# TH8_Breakout_cryo.net
KiCad netlist of a schematic drawn in Altium Designer
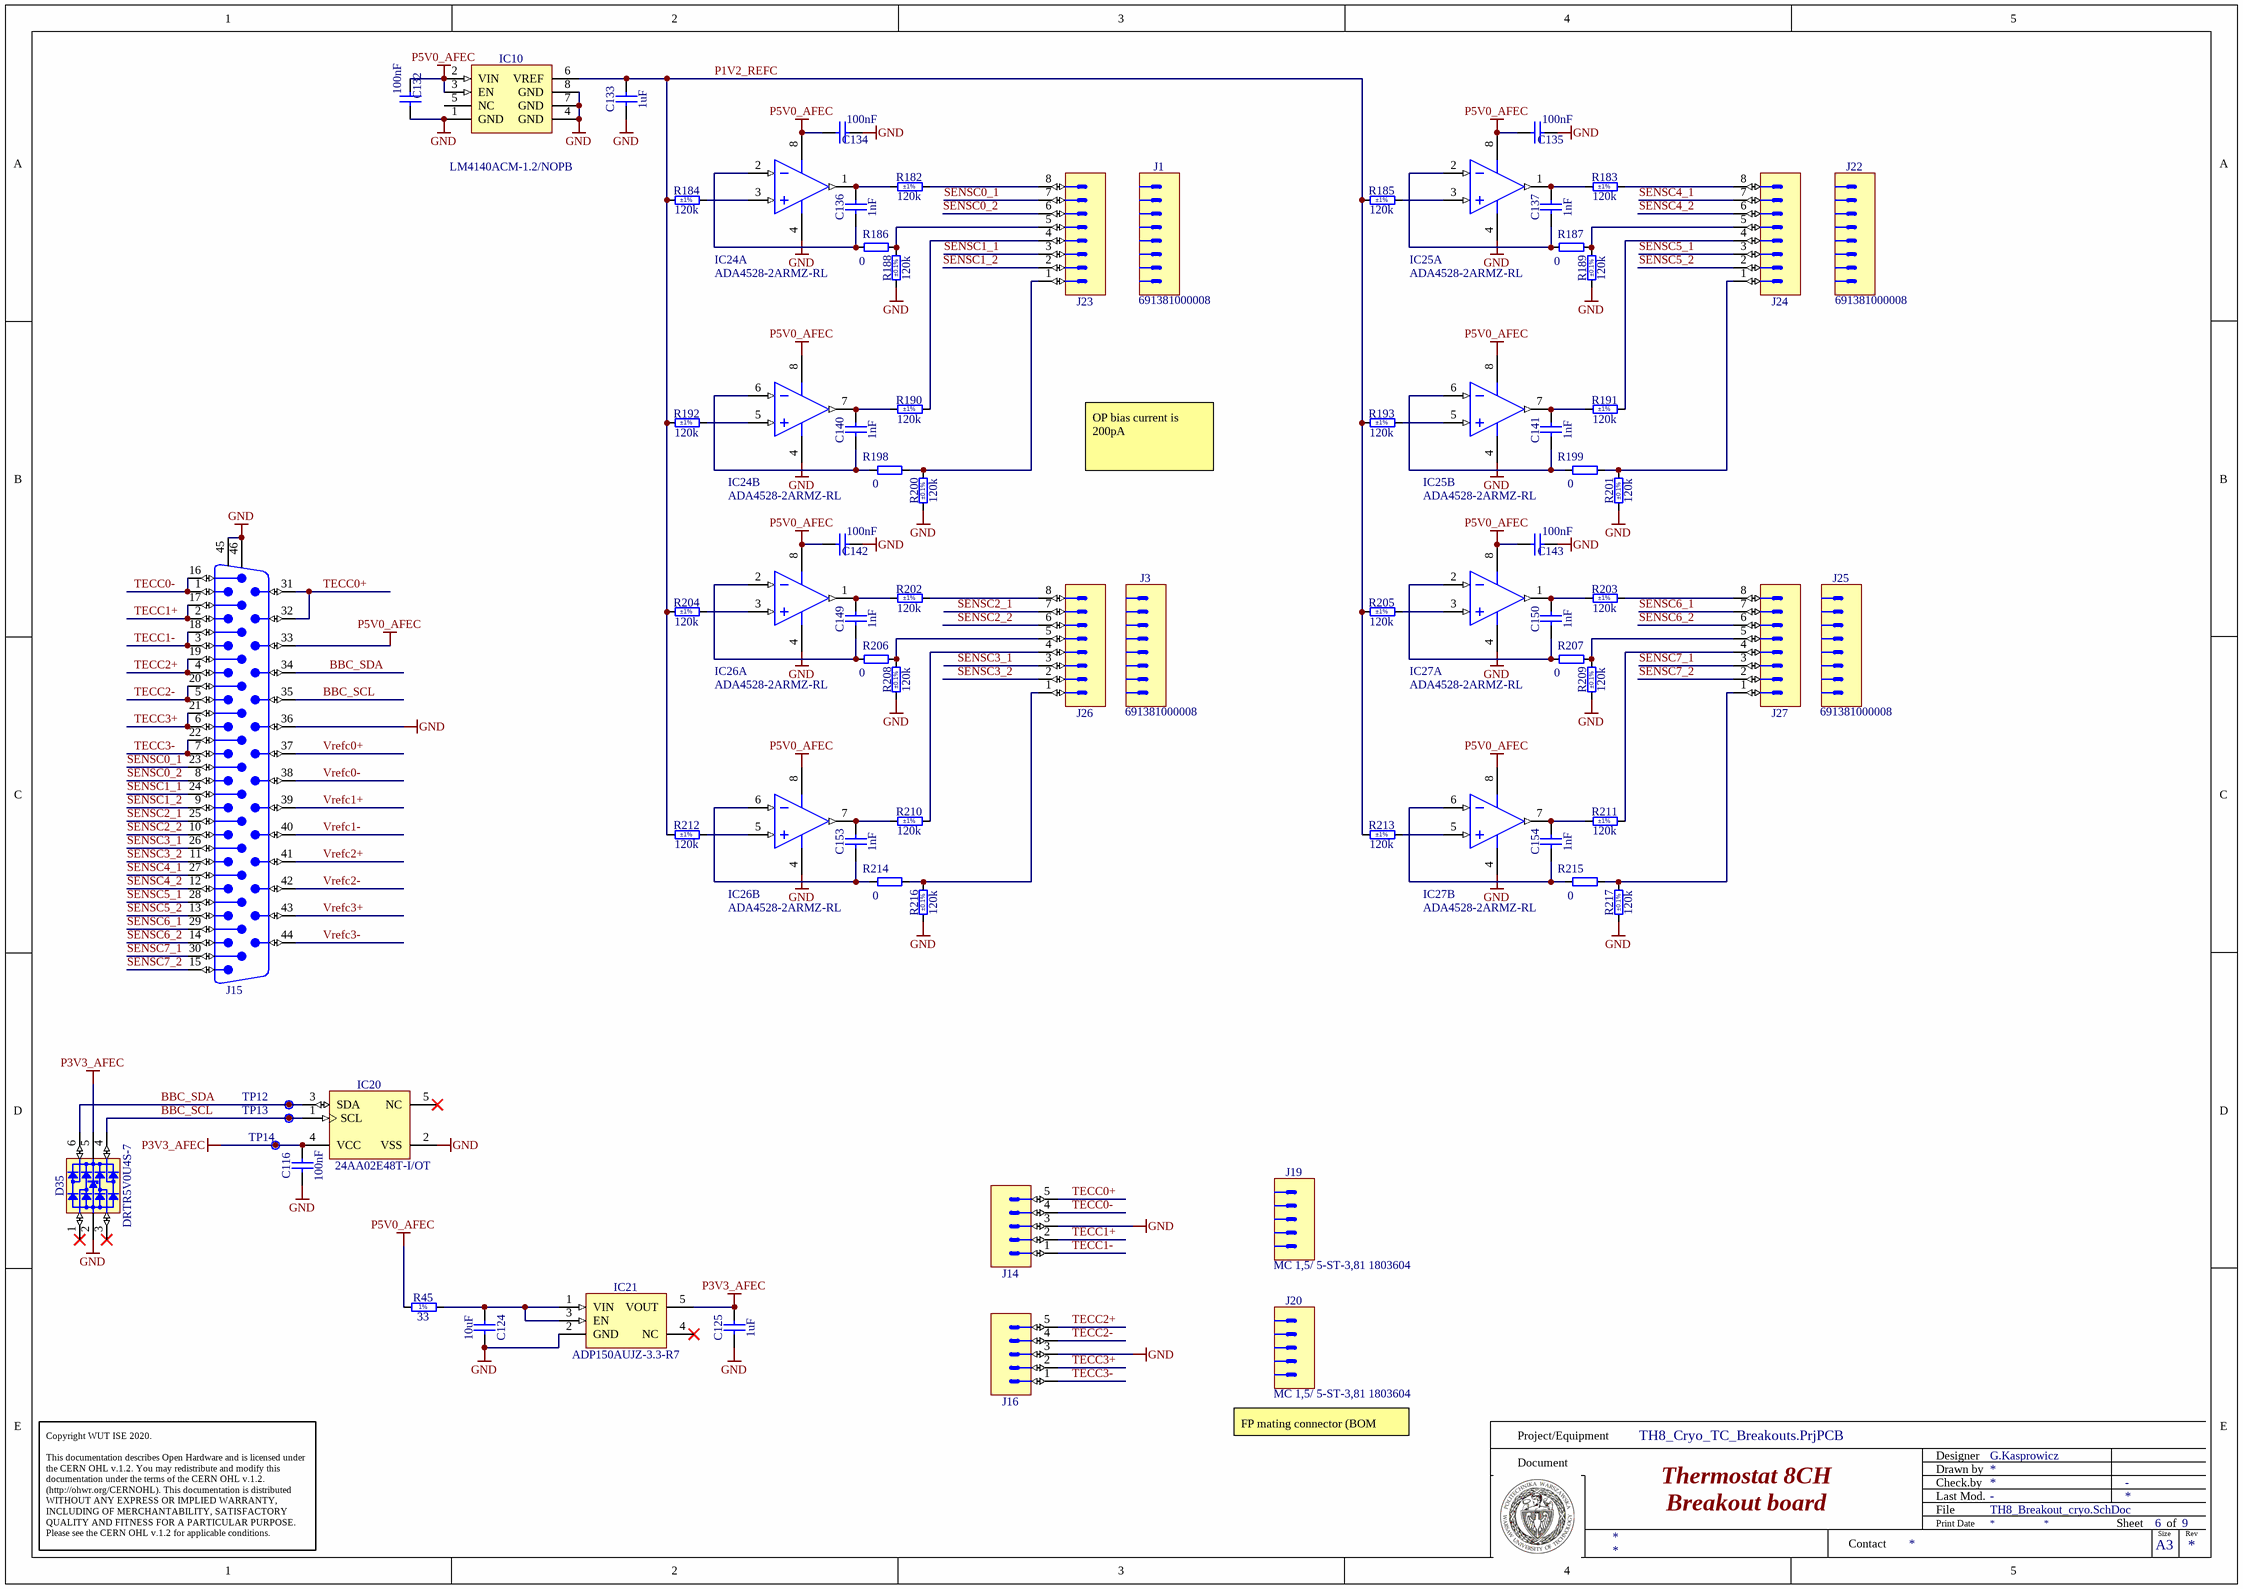
[diagram p0: TH8_Breakout_cryo.SchDoc]

(export (version "E")
  (design (tool "Eeschema 10.0.6"))
  (components
    (comp (ref "C116")
      (value "100nF")
      (footprint "CAPC1005X55N")
      (description "Non-polarised capacitor")
      (fields
        (field (name "PART NUMBER") "CC0402_100NF_16V_10%_X5R")
        (field (name "VOLTAGE") "16V")
        (field (name "AUTHOR") "CERN DEM JLC")
      )
      (libsource (lib "Capacitors") (part "Capacitor - non polarized"))
    )
    (comp (ref "C124")
      (value "10uF")
      (footprint "CAPC2012X135N")
      (description "Non-polarised capacitor")
      (fields
        (field (name "PART NUMBER") "CC0805_10UF_16V_10%_X5R")
        (field (name "VOLTAGE") "16V")
        (field (name "AUTHOR") "CERN DEM JLC")
      )
      (libsource (lib "Capacitors") (part "Capacitor - non polarized"))
    )
    (comp (ref "C125")
      (value "1uF")
      (footprint "CAPC1608X87N")
      (description "Non-polarised capacitor")
      (fields
        (field (name "PART NUMBER") "CC0603_1UF_25V_10%_X7R")
        (field (name "VOLTAGE") "25V")
        (field (name "AUTHOR") "CERN DEM JLC")
      )
      (libsource (lib "Capacitors") (part "Capacitor - non polarized"))
    )
    (comp (ref "C132")
      (value "100nF")
      (footprint "CAPC1005X55N")
      (description "Non-polarised capacitor")
      (fields
        (field (name "PART NUMBER") "CC0402_100NF_16V_10%_X5R")
        (field (name "VOLTAGE") "16V")
        (field (name "AUTHOR") "CERN DEM JLC")
      )
      (libsource (lib "Capacitors") (part "Capacitor - non polarized"))
    )
    (comp (ref "C133")
      (value "1uF")
      (footprint "CAPC1608X87N")
      (description "Non-polarised capacitor")
      (fields
        (field (name "PART NUMBER") "CC0603_1UF_25V_10%_X7R")
        (field (name "VOLTAGE") "25V")
        (field (name "AUTHOR") "CERN DEM JLC")
      )
      (libsource (lib "Capacitors") (part "Capacitor - non polarized"))
    )
    (comp (ref "C134")
      (value "100nF")
      (footprint "CAPC1005X55N")
      (description "Non-polarised capacitor")
      (fields
        (field (name "PART NUMBER") "CC0402_100NF_16V_10%_X5R")
        (field (name "VOLTAGE") "16V")
        (field (name "AUTHOR") "CERN DEM JLC")
      )
      (libsource (lib "Capacitors") (part "Capacitor - non polarized"))
    )
    (comp (ref "C135")
      (value "100nF")
      (footprint "CAPC1005X55N")
      (description "Non-polarised capacitor")
      (fields
        (field (name "PART NUMBER") "CC0402_100NF_16V_10%_X5R")
        (field (name "VOLTAGE") "16V")
        (field (name "AUTHOR") "CERN DEM JLC")
      )
      (libsource (lib "Capacitors") (part "Capacitor - non polarized"))
    )
    (comp (ref "C136")
      (value "1nF")
      (footprint "CAPC1005X55N")
      (description "Non-polarised capacitor")
      (fields
        (field (name "PART NUMBER") "CC0402_1NF_50V_10%_X7R")
        (field (name "VOLTAGE") "50V")
        (field (name "AUTHOR") "CERN DEM JLC")
      )
      (libsource (lib "Capacitors") (part "Capacitor - non polarized"))
    )
    (comp (ref "C137")
      (value "1nF")
      (footprint "CAPC1005X55N")
      (description "Non-polarised capacitor")
      (fields
        (field (name "PART NUMBER") "CC0402_1NF_50V_10%_X7R")
        (field (name "VOLTAGE") "50V")
        (field (name "AUTHOR") "CERN DEM JLC")
      )
      (libsource (lib "Capacitors") (part "Capacitor - non polarized"))
    )
    (comp (ref "C140")
      (value "1nF")
      (footprint "CAPC1005X55N")
      (description "Non-polarised capacitor")
      (fields
        (field (name "PART NUMBER") "CC0402_1NF_50V_10%_X7R")
        (field (name "VOLTAGE") "50V")
        (field (name "AUTHOR") "CERN DEM JLC")
      )
      (libsource (lib "Capacitors") (part "Capacitor - non polarized"))
    )
    (comp (ref "C141")
      (value "1nF")
      (footprint "CAPC1005X55N")
      (description "Non-polarised capacitor")
      (fields
        (field (name "PART NUMBER") "CC0402_1NF_50V_10%_X7R")
        (field (name "VOLTAGE") "50V")
        (field (name "AUTHOR") "CERN DEM JLC")
      )
      (libsource (lib "Capacitors") (part "Capacitor - non polarized"))
    )
    (comp (ref "C142")
      (value "100nF")
      (footprint "CAPC1005X55N")
      (description "Non-polarised capacitor")
      (fields
        (field (name "PART NUMBER") "CC0402_100NF_16V_10%_X5R")
        (field (name "VOLTAGE") "16V")
        (field (name "AUTHOR") "CERN DEM JLC")
      )
      (libsource (lib "Capacitors") (part "Capacitor - non polarized"))
    )
    (comp (ref "C143")
      (value "100nF")
      (footprint "CAPC1005X55N")
      (description "Non-polarised capacitor")
      (fields
        (field (name "PART NUMBER") "CC0402_100NF_16V_10%_X5R")
        (field (name "VOLTAGE") "16V")
        (field (name "AUTHOR") "CERN DEM JLC")
      )
      (libsource (lib "Capacitors") (part "Capacitor - non polarized"))
    )
    (comp (ref "C149")
      (value "1nF")
      (footprint "CAPC1005X55N")
      (description "Non-polarised capacitor")
      (fields
        (field (name "PART NUMBER") "CC0402_1NF_50V_10%_X7R")
        (field (name "VOLTAGE") "50V")
        (field (name "AUTHOR") "CERN DEM JLC")
      )
      (libsource (lib "Capacitors") (part "Capacitor - non polarized"))
    )
    (comp (ref "C150")
      (value "1nF")
      (footprint "CAPC1005X55N")
      (description "Non-polarised capacitor")
      (fields
        (field (name "PART NUMBER") "CC0402_1NF_50V_10%_X7R")
        (field (name "VOLTAGE") "50V")
        (field (name "AUTHOR") "CERN DEM JLC")
      )
      (libsource (lib "Capacitors") (part "Capacitor - non polarized"))
    )
    (comp (ref "C153")
      (value "1nF")
      (footprint "CAPC1005X55N")
      (description "Non-polarised capacitor")
      (fields
        (field (name "PART NUMBER") "CC0402_1NF_50V_10%_X7R")
        (field (name "VOLTAGE") "50V")
        (field (name "AUTHOR") "CERN DEM JLC")
      )
      (libsource (lib "Capacitors") (part "Capacitor - non polarized"))
    )
    (comp (ref "C154")
      (value "1nF")
      (footprint "CAPC1005X55N")
      (description "Non-polarised capacitor")
      (fields
        (field (name "PART NUMBER") "CC0402_1NF_50V_10%_X7R")
        (field (name "VOLTAGE") "50V")
        (field (name "AUTHOR") "CERN DEM JLC")
      )
      (libsource (lib "Capacitors") (part "Capacitor - non polarized"))
    )
    (comp (ref "D35")
      (value "DRTR5V0U4S-7")
      (footprint "SOT65P210X110-6N")
      (description "Integrated Quad Ultra-Low Capacitance ESD Protection")
      (fields (field (name "MANUFACTURER") "DIODES") (field (name "AUTHOR") "GK"))
      (libsource (lib "Diodes") (part "D_TVS_DRTR5V0U4S-7"))
    )
    (comp (ref "IC10")
      (value "LM4140ACM-1.2/NOPB")
      (footprint "SOIC127P600X175-8N")
      (description "High Precision Low Noise Low Dropout Voltage Reference")
      (fields (field (name "MANUFACTURER") "TEXAS INSTRUMENTS") (field (name "AUTHOR") "CERN DEM JLC"))
      (libsource (lib "ICs And Semiconductors") (part "LM4140"))
    )
    (comp (ref "IC20")
      (value "24AA02E48T-I/OT")
      (footprint "SOT95P280X145-5N")
      (description "1.7V-5.5V, 2K I2C Serial EEPROM With EUI-48 Node Identity")
      (fields (field (name "MANUFACTURER") "MICROCHIP TECHNOLOGY") (field (name "AUTHOR") "CERN DEM MR"))
      (libsource (lib "ICs And Semiconductors") (part "24AA02E48T-I/OT"))
    )
    (comp (ref "IC21")
      (value "ADP150AUJZ-3.3-R7")
      (footprint "SOT95P280X90-5N")
      (description "Ultralow Noise, 150 mA CMOS Linear Regulator")
      (fields (field (name "MANUFACTURER") "ANALOG DEVICES") (field (name "AUTHOR") "CERN DEM JLC"))
      (libsource (lib "ICs And Semiconductors") (part "ADP150AUJZ"))
    )
    (comp (ref "IC24")
      (value "ADA4528-2ARMZ-RL")
      (footprint "ADI-RM-8_N")
      (fields (field (name "GENERIC PART NUMBER") "ADA4528-2") (field (name "MANUFACTURER") "Analog Devices"))
      (libsource (lib "Altium Content Vault") (part "ADI-ADA4000-2-X-8"))
    )
    (comp (ref "IC25")
      (value "ADA4528-2ARMZ-RL")
      (footprint "ADI-RM-8_N")
      (fields (field (name "GENERIC PART NUMBER") "ADA4528-2") (field (name "MANUFACTURER") "Analog Devices"))
      (libsource (lib "Altium Content Vault") (part "ADI-ADA4000-2-X-8"))
    )
    (comp (ref "IC26")
      (value "ADA4528-2ARMZ-RL")
      (footprint "ADI-RM-8_N")
      (fields (field (name "GENERIC PART NUMBER") "ADA4528-2") (field (name "MANUFACTURER") "Analog Devices"))
      (libsource (lib "Altium Content Vault") (part "ADI-ADA4000-2-X-8"))
    )
    (comp (ref "IC27")
      (value "ADA4528-2ARMZ-RL")
      (footprint "ADI-RM-8_N")
      (fields (field (name "GENERIC PART NUMBER") "ADA4528-2") (field (name "MANUFACTURER") "Analog Devices"))
      (libsource (lib "Altium Content Vault") (part "ADI-ADA4000-2-X-8"))
    )
    (comp (ref "J1")
      (value "691381000008")
      (footprint "WURTH_691381000008")
      (description "Phoenix Contact 2.5 pitch terminal plug, 8 ways")
      (fields (field (name "MANUFACTURER") "WURTH") (field (name "MANUFACTURER PART NUMBER") "691381000008"))
      (libsource (lib "Connectors") (part "CON_TB_WURTH_691381000008"))
    )
    (comp (ref "J3")
      (value "691381000008")
      (footprint "WURTH_691381000008")
      (description "Phoenix Contact 2.5 pitch terminal plug, 8 ways")
      (fields (field (name "MANUFACTURER") "WURTH") (field (name "MANUFACTURER PART NUMBER") "691381000008"))
      (libsource (lib "Connectors") (part "CON_TB_WURTH_691381000008"))
    )
    (comp (ref "J14")
      (value "~")
      (footprint "PHOENIX_1803455")
      (description "Connector 5 Male")
      (fields
        (field (name "PART NUMBER") "PHOENIX_1803455")
        (field (name "MANUFACTURER") "PHOENIX CONTACT")
        (field (name "AUTHOR") "CERN DEM JLC")
      )
      (libsource (lib "Connectors") (part "Connector 5 Male"))
    )
    (comp (ref "J15")
      (value "D-Sub")
      (footprint "AMPHENOL_10090926-P444XLF")
      (description "Connector D-sub 44 Male")
      (fields
        (field (name "PART NUMBER") "AMPHENOL_10090926-P444XLF")
        (field (name "MANUFACTURER") "AMPHENOL")
        (field (name "AUTHOR") "CERN DEM BC")
      )
      (libsource (lib "Connectors") (part "Connector D-sub 44 Male"))
    )
    (comp (ref "J16")
      (value "~")
      (footprint "PHOENIX_1803455")
      (description "Connector 5 Male")
      (fields
        (field (name "PART NUMBER") "PHOENIX_1803455")
        (field (name "MANUFACTURER") "PHOENIX CONTACT")
        (field (name "AUTHOR") "CERN DEM JLC")
      )
      (libsource (lib "Connectors") (part "Connector 5 Male"))
    )
    (comp (ref "J19")
      (value "~")
      (footprint "PHOENIX_1803604")
      (description "Phoenix Contact 3.81 pitch terminal plug, 5 ways")
      (fields
        (field (name "MANUFACTURER") "Phoenix Contact")
        (field (name "MANUFACTURER PART NUMBER") "MC 1,5/ 5-ST-3,81 1803604")
      )
      (libsource (lib "Connectors") (part "PHOENIX_1803604"))
    )
    (comp (ref "J20")
      (value "~")
      (footprint "PHOENIX_1803604")
      (description "Phoenix Contact 3.81 pitch terminal plug, 5 ways")
      (fields
        (field (name "MANUFACTURER") "Phoenix Contact")
        (field (name "MANUFACTURER PART NUMBER") "MC 1,5/ 5-ST-3,81 1803604")
      )
      (libsource (lib "Connectors") (part "PHOENIX_1803604"))
    )
    (comp (ref "J22")
      (value "691381000008")
      (footprint "WURTH_691381000008")
      (description "Phoenix Contact 2.5 pitch terminal plug, 8 ways")
      (fields (field (name "MANUFACTURER") "WURTH") (field (name "MANUFACTURER PART NUMBER") "691381000008"))
      (libsource (lib "Connectors") (part "CON_TB_WURTH_691381000008"))
    )
    (comp (ref "J23")
      (value "~")
      (footprint "PHOENIX_1881613")
      (description "Connector 8 Male")
      (fields
        (field (name "PART NUMBER") "PHOENIX_1881613")
        (field (name "MANUFACTURER") "PHOENIX CONTACT")
        (field (name "AUTHOR") "CERN DEM JLC")
      )
      (libsource (lib "Connectors") (part "Connector 8 Male"))
    )
    (comp (ref "J24")
      (value "~")
      (footprint "PHOENIX_1881613")
      (description "Connector 8 Male")
      (fields
        (field (name "PART NUMBER") "PHOENIX_1881613")
        (field (name "MANUFACTURER") "PHOENIX CONTACT")
        (field (name "AUTHOR") "CERN DEM JLC")
      )
      (libsource (lib "Connectors") (part "Connector 8 Male"))
    )
    (comp (ref "J25")
      (value "691381000008")
      (footprint "WURTH_691381000008")
      (description "Phoenix Contact 2.5 pitch terminal plug, 8 ways")
      (fields (field (name "MANUFACTURER") "WURTH") (field (name "MANUFACTURER PART NUMBER") "691381000008"))
      (libsource (lib "Connectors") (part "CON_TB_WURTH_691381000008"))
    )
    (comp (ref "J26")
      (value "~")
      (footprint "PHOENIX_1881613")
      (description "Connector 8 Male")
      (fields
        (field (name "PART NUMBER") "PHOENIX_1881613")
        (field (name "MANUFACTURER") "PHOENIX CONTACT")
        (field (name "AUTHOR") "CERN DEM JLC")
      )
      (libsource (lib "Connectors") (part "Connector 8 Male"))
    )
    (comp (ref "J27")
      (value "~")
      (footprint "PHOENIX_1881613")
      (description "Connector 8 Male")
      (fields
        (field (name "PART NUMBER") "PHOENIX_1881613")
        (field (name "MANUFACTURER") "PHOENIX CONTACT")
        (field (name "AUTHOR") "CERN DEM JLC")
      )
      (libsource (lib "Connectors") (part "Connector 8 Male"))
    )
    (comp (ref "R45")
      (value "33")
      (footprint "RESC1005X40N")
      (description "Resistor - 1%")
      (fields
        (field (name "PART NUMBER") "R0402_33R_1%_0.0625W_100PPM")
        (field (name "POWER") "0.0625W")
        (field (name "AUTHOR") "CERN DEM JLC")
      )
      (libsource (lib "Resistors") (part "Resistor - 1%"))
    )
    (comp (ref "R182")
      (value "120k")
      (footprint "RESC1005X40N")
      (description "Resistor - 1%")
      (fields
        (field (name "TOLERANCE") "±1%")
        (field (name "PART NUMBER") "R0402_120K_1%_0.0625W_100PPM")
        (field (name "POWER") "0.0625W")
        (field (name "AUTHOR") "CERN DEM JLC")
      )
      (libsource (lib "Resistors") (part "Resistor - 1%"))
    )
    (comp (ref "R183")
      (value "120k")
      (footprint "RESC1005X40N")
      (description "Resistor - 1%")
      (fields
        (field (name "TOLERANCE") "±1%")
        (field (name "PART NUMBER") "R0402_120K_1%_0.0625W_100PPM")
        (field (name "POWER") "0.0625W")
        (field (name "AUTHOR") "CERN DEM JLC")
      )
      (libsource (lib "Resistors") (part "Resistor - 1%"))
    )
    (comp (ref "R184")
      (value "120k")
      (footprint "RESC1005X40N")
      (description "Resistor - 1%")
      (fields
        (field (name "TOLERANCE") "±1%")
        (field (name "PART NUMBER") "R0402_120K_1%_0.0625W_100PPM")
        (field (name "POWER") "0.0625W")
        (field (name "AUTHOR") "CERN DEM JLC")
      )
      (libsource (lib "Resistors") (part "Resistor - 1%"))
    )
    (comp (ref "R185")
      (value "120k")
      (footprint "RESC1005X40N")
      (description "Resistor - 1%")
      (fields
        (field (name "TOLERANCE") "±1%")
        (field (name "PART NUMBER") "R0402_120K_1%_0.0625W_100PPM")
        (field (name "POWER") "0.0625W")
        (field (name "AUTHOR") "CERN DEM JLC")
      )
      (libsource (lib "Resistors") (part "Resistor - 1%"))
    )
    (comp (ref "R186")
      (value "0")
      (footprint "RESC1608X55N")
      (description "Resistor")
      (fields
        (field (name "PART NUMBER") "R0603_0R_JUMPER")
        (field (name "MANUFACTURER") "GENERIC")
        (field (name "AUTHOR") "CERN DEM JLC")
      )
      (libsource (lib "Resistors") (part "Resistor"))
    )
    (comp (ref "R187")
      (value "0")
      (footprint "RESC1608X55N")
      (description "Resistor")
      (fields
        (field (name "PART NUMBER") "R0603_0R_JUMPER")
        (field (name "MANUFACTURER") "GENERIC")
        (field (name "AUTHOR") "CERN DEM JLC")
      )
      (libsource (lib "Resistors") (part "Resistor"))
    )
    (comp (ref "R188")
      (value "120k")
      (footprint "RESC2012X60N")
      (description "Resistor - 0.1%")
      (fields
        (field (name "TOLERANCE") "±0.1%")
        (field (name "PART NUMBER") "R0805_120K_0.1%_0.125W_25PPM")
        (field (name "POWER") "0.125W")
        (field (name "AUTHOR") "CERN DEM JLC")
      )
      (libsource (lib "Resistors") (part "Resistor - 0.1%"))
    )
    (comp (ref "R189")
      (value "120k")
      (footprint "RESC2012X60N")
      (description "Resistor - 0.1%")
      (fields
        (field (name "TOLERANCE") "±0.1%")
        (field (name "PART NUMBER") "R0805_120K_0.1%_0.125W_25PPM")
        (field (name "POWER") "0.125W")
        (field (name "AUTHOR") "CERN DEM JLC")
      )
      (libsource (lib "Resistors") (part "Resistor - 0.1%"))
    )
    (comp (ref "R190")
      (value "120k")
      (footprint "RESC1005X40N")
      (description "Resistor - 1%")
      (fields
        (field (name "TOLERANCE") "±1%")
        (field (name "PART NUMBER") "R0402_120K_1%_0.0625W_100PPM")
        (field (name "POWER") "0.0625W")
        (field (name "AUTHOR") "CERN DEM JLC")
      )
      (libsource (lib "Resistors") (part "Resistor - 1%"))
    )
    (comp (ref "R191")
      (value "120k")
      (footprint "RESC1005X40N")
      (description "Resistor - 1%")
      (fields
        (field (name "TOLERANCE") "±1%")
        (field (name "PART NUMBER") "R0402_120K_1%_0.0625W_100PPM")
        (field (name "POWER") "0.0625W")
        (field (name "AUTHOR") "CERN DEM JLC")
      )
      (libsource (lib "Resistors") (part "Resistor - 1%"))
    )
    (comp (ref "R192")
      (value "120k")
      (footprint "RESC1005X40N")
      (description "Resistor - 1%")
      (fields
        (field (name "TOLERANCE") "±1%")
        (field (name "PART NUMBER") "R0402_120K_1%_0.0625W_100PPM")
        (field (name "POWER") "0.0625W")
        (field (name "AUTHOR") "CERN DEM JLC")
      )
      (libsource (lib "Resistors") (part "Resistor - 1%"))
    )
    (comp (ref "R193")
      (value "120k")
      (footprint "RESC1005X40N")
      (description "Resistor - 1%")
      (fields
        (field (name "TOLERANCE") "±1%")
        (field (name "PART NUMBER") "R0402_120K_1%_0.0625W_100PPM")
        (field (name "POWER") "0.0625W")
        (field (name "AUTHOR") "CERN DEM JLC")
      )
      (libsource (lib "Resistors") (part "Resistor - 1%"))
    )
    (comp (ref "R198")
      (value "0")
      (footprint "RESC1608X55N")
      (description "Resistor")
      (fields
        (field (name "PART NUMBER") "R0603_0R_JUMPER")
        (field (name "MANUFACTURER") "GENERIC")
        (field (name "AUTHOR") "CERN DEM JLC")
      )
      (libsource (lib "Resistors") (part "Resistor"))
    )
    (comp (ref "R199")
      (value "0")
      (footprint "RESC1608X55N")
      (description "Resistor")
      (fields
        (field (name "PART NUMBER") "R0603_0R_JUMPER")
        (field (name "MANUFACTURER") "GENERIC")
        (field (name "AUTHOR") "CERN DEM JLC")
      )
      (libsource (lib "Resistors") (part "Resistor"))
    )
    (comp (ref "R200")
      (value "120k")
      (footprint "RESC2012X60N")
      (description "Resistor - 0.1%")
      (fields
        (field (name "TOLERANCE") "±0.1%")
        (field (name "PART NUMBER") "R0805_120K_0.1%_0.125W_25PPM")
        (field (name "POWER") "0.125W")
        (field (name "AUTHOR") "CERN DEM JLC")
      )
      (libsource (lib "Resistors") (part "Resistor - 0.1%"))
    )
    (comp (ref "R201")
      (value "120k")
      (footprint "RESC2012X60N")
      (description "Resistor - 0.1%")
      (fields
        (field (name "TOLERANCE") "±0.1%")
        (field (name "PART NUMBER") "R0805_120K_0.1%_0.125W_25PPM")
        (field (name "POWER") "0.125W")
        (field (name "AUTHOR") "CERN DEM JLC")
      )
      (libsource (lib "Resistors") (part "Resistor - 0.1%"))
    )
    (comp (ref "R202")
      (value "120k")
      (footprint "RESC1005X40N")
      (description "Resistor - 1%")
      (fields
        (field (name "TOLERANCE") "±1%")
        (field (name "PART NUMBER") "R0402_120K_1%_0.0625W_100PPM")
        (field (name "POWER") "0.0625W")
        (field (name "AUTHOR") "CERN DEM JLC")
      )
      (libsource (lib "Resistors") (part "Resistor - 1%"))
    )
    (comp (ref "R203")
      (value "120k")
      (footprint "RESC1005X40N")
      (description "Resistor - 1%")
      (fields
        (field (name "TOLERANCE") "±1%")
        (field (name "PART NUMBER") "R0402_120K_1%_0.0625W_100PPM")
        (field (name "POWER") "0.0625W")
        (field (name "AUTHOR") "CERN DEM JLC")
      )
      (libsource (lib "Resistors") (part "Resistor - 1%"))
    )
    (comp (ref "R204")
      (value "120k")
      (footprint "RESC1005X40N")
      (description "Resistor - 1%")
      (fields
        (field (name "TOLERANCE") "±1%")
        (field (name "PART NUMBER") "R0402_120K_1%_0.0625W_100PPM")
        (field (name "POWER") "0.0625W")
        (field (name "AUTHOR") "CERN DEM JLC")
      )
      (libsource (lib "Resistors") (part "Resistor - 1%"))
    )
    (comp (ref "R205")
      (value "120k")
      (footprint "RESC1005X40N")
      (description "Resistor - 1%")
      (fields
        (field (name "TOLERANCE") "±1%")
        (field (name "PART NUMBER") "R0402_120K_1%_0.0625W_100PPM")
        (field (name "POWER") "0.0625W")
        (field (name "AUTHOR") "CERN DEM JLC")
      )
      (libsource (lib "Resistors") (part "Resistor - 1%"))
    )
    (comp (ref "R206")
      (value "0")
      (footprint "RESC1608X55N")
      (description "Resistor")
      (fields
        (field (name "PART NUMBER") "R0603_0R_JUMPER")
        (field (name "MANUFACTURER") "GENERIC")
        (field (name "AUTHOR") "CERN DEM JLC")
      )
      (libsource (lib "Resistors") (part "Resistor"))
    )
    (comp (ref "R207")
      (value "0")
      (footprint "RESC1608X55N")
      (description "Resistor")
      (fields
        (field (name "PART NUMBER") "R0603_0R_JUMPER")
        (field (name "MANUFACTURER") "GENERIC")
        (field (name "AUTHOR") "CERN DEM JLC")
      )
      (libsource (lib "Resistors") (part "Resistor"))
    )
    (comp (ref "R208")
      (value "120k")
      (footprint "RESC2012X60N")
      (description "Resistor - 0.1%")
      (fields
        (field (name "TOLERANCE") "±0.1%")
        (field (name "PART NUMBER") "R0805_120K_0.1%_0.125W_25PPM")
        (field (name "POWER") "0.125W")
        (field (name "AUTHOR") "CERN DEM JLC")
      )
      (libsource (lib "Resistors") (part "Resistor - 0.1%"))
    )
    (comp (ref "R209")
      (value "120k")
      (footprint "RESC2012X60N")
      (description "Resistor - 0.1%")
      (fields
        (field (name "TOLERANCE") "±0.1%")
        (field (name "PART NUMBER") "R0805_120K_0.1%_0.125W_25PPM")
        (field (name "POWER") "0.125W")
        (field (name "AUTHOR") "CERN DEM JLC")
      )
      (libsource (lib "Resistors") (part "Resistor - 0.1%"))
    )
    (comp (ref "R210")
      (value "120k")
      (footprint "RESC1005X40N")
      (description "Resistor - 1%")
      (fields
        (field (name "TOLERANCE") "±1%")
        (field (name "PART NUMBER") "R0402_120K_1%_0.0625W_100PPM")
        (field (name "POWER") "0.0625W")
        (field (name "AUTHOR") "CERN DEM JLC")
      )
      (libsource (lib "Resistors") (part "Resistor - 1%"))
    )
    (comp (ref "R211")
      (value "120k")
      (footprint "RESC1005X40N")
      (description "Resistor - 1%")
      (fields
        (field (name "TOLERANCE") "±1%")
        (field (name "PART NUMBER") "R0402_120K_1%_0.0625W_100PPM")
        (field (name "POWER") "0.0625W")
        (field (name "AUTHOR") "CERN DEM JLC")
      )
      (libsource (lib "Resistors") (part "Resistor - 1%"))
    )
    (comp (ref "R212")
      (value "120k")
      (footprint "RESC1005X40N")
      (description "Resistor - 1%")
      (fields
        (field (name "TOLERANCE") "±1%")
        (field (name "PART NUMBER") "R0402_120K_1%_0.0625W_100PPM")
        (field (name "POWER") "0.0625W")
        (field (name "AUTHOR") "CERN DEM JLC")
      )
      (libsource (lib "Resistors") (part "Resistor - 1%"))
    )
    (comp (ref "R213")
      (value "120k")
      (footprint "RESC1005X40N")
      (description "Resistor - 1%")
      (fields
        (field (name "TOLERANCE") "±1%")
        (field (name "PART NUMBER") "R0402_120K_1%_0.0625W_100PPM")
        (field (name "POWER") "0.0625W")
        (field (name "AUTHOR") "CERN DEM JLC")
      )
      (libsource (lib "Resistors") (part "Resistor - 1%"))
    )
    (comp (ref "R214")
      (value "0")
      (footprint "RESC1608X55N")
      (description "Resistor")
      (fields
        (field (name "PART NUMBER") "R0603_0R_JUMPER")
        (field (name "MANUFACTURER") "GENERIC")
        (field (name "AUTHOR") "CERN DEM JLC")
      )
      (libsource (lib "Resistors") (part "Resistor"))
    )
    (comp (ref "R215")
      (value "0")
      (footprint "RESC1608X55N")
      (description "Resistor")
      (fields
        (field (name "PART NUMBER") "R0603_0R_JUMPER")
        (field (name "MANUFACTURER") "GENERIC")
        (field (name "AUTHOR") "CERN DEM JLC")
      )
      (libsource (lib "Resistors") (part "Resistor"))
    )
    (comp (ref "R216")
      (value "120k")
      (footprint "RESC2012X60N")
      (description "Resistor - 0.1%")
      (fields
        (field (name "TOLERANCE") "±0.1%")
        (field (name "PART NUMBER") "R0805_120K_0.1%_0.125W_25PPM")
        (field (name "POWER") "0.125W")
        (field (name "AUTHOR") "CERN DEM JLC")
      )
      (libsource (lib "Resistors") (part "Resistor - 0.1%"))
    )
    (comp (ref "R217")
      (value "120k")
      (footprint "RESC2012X60N")
      (description "Resistor - 0.1%")
      (fields
        (field (name "TOLERANCE") "±0.1%")
        (field (name "PART NUMBER") "R0805_120K_0.1%_0.125W_25PPM")
        (field (name "POWER") "0.125W")
        (field (name "AUTHOR") "CERN DEM JLC")
      )
      (libsource (lib "Resistors") (part "Resistor - 0.1%"))
    )
    (comp (ref "TP12")
      (value "Test Point")
      (footprint "TPS127")
      (fields (field (name "PART NUMBER") "SMD_PAD_1.27X1.27MM") (field (name "AUTHOR") "CERN DEM JLC"))
      (libsource (lib "Eletro-mechanical") (part "Test Point"))
    )
    (comp (ref "TP13")
      (value "Test Point")
      (footprint "TPS127")
      (fields (field (name "PART NUMBER") "SMD_PAD_1.27X1.27MM") (field (name "AUTHOR") "CERN DEM JLC"))
      (libsource (lib "Eletro-mechanical") (part "Test Point"))
    )
    (comp (ref "TP14")
      (value "Test Point")
      (footprint "TPS127")
      (fields (field (name "PART NUMBER") "SMD_PAD_1.27X1.27MM") (field (name "AUTHOR") "CERN DEM JLC"))
      (libsource (lib "Eletro-mechanical") (part "Test Point"))
    )
  )
  (nets
    (net (code "1") (name "/BBC_SCL") (class "Default")
      (node (ref "D35") (pin "4") (pinfunction "I/O3_4") (pintype "bidirectional"))
      (node (ref "IC20") (pin "1") (pinfunction "SCL_1") (pintype "input"))
      (node (ref "J15") (pin "35") (pinfunction "35_35") (pintype "bidirectional"))
      (node (ref "TP13") (pin "1") (pinfunction "1_1") (pintype "bidirectional"))
    )
    (net (code "2") (name "/BBC_SDA") (class "Default")
      (node (ref "D35") (pin "6") (pinfunction "I/O4_6") (pintype "bidirectional"))
      (node (ref "IC20") (pin "3") (pinfunction "SDA_3") (pintype "bidirectional"))
      (node (ref "J15") (pin "34") (pinfunction "34_34") (pintype "bidirectional"))
      (node (ref "TP12") (pin "1") (pinfunction "1_1") (pintype "bidirectional"))
    )
    (net (code "3") (name "/P1V2_REFC") (class "Default")
      (node (ref "C133") (pin "2") (pinfunction "2_2") (pintype "passive"))
      (node (ref "IC10") (pin "6") (pinfunction "VREF_6") (pintype "power_in"))
      (node (ref "R184") (pin "1") (pinfunction "1_1") (pintype "passive"))
      (node (ref "R185") (pin "1") (pinfunction "1_1") (pintype "passive"))
      (node (ref "R192") (pin "1") (pinfunction "1_1") (pintype "passive"))
      (node (ref "R193") (pin "1") (pinfunction "1_1") (pintype "passive"))
      (node (ref "R204") (pin "1") (pinfunction "1_1") (pintype "passive"))
      (node (ref "R205") (pin "1") (pinfunction "1_1") (pintype "passive"))
      (node (ref "R212") (pin "1") (pinfunction "1_1") (pintype "passive"))
      (node (ref "R213") (pin "1") (pinfunction "1_1") (pintype "passive"))
    )
    (net (code "4") (name "/SENSC0_1") (class "Default")
      (node (ref "J15") (pin "23") (pinfunction "23_23") (pintype "bidirectional"))
      (node (ref "J23") (pin "7") (pinfunction "7_7") (pintype "bidirectional"))
    )
    (net (code "5") (name "/SENSC0_2") (class "Default")
      (node (ref "J15") (pin "8") (pinfunction "8_8") (pintype "bidirectional"))
      (node (ref "J23") (pin "6") (pinfunction "6_6") (pintype "bidirectional"))
    )
    (net (code "6") (name "/SENSC1_1") (class "Default")
      (node (ref "J15") (pin "24") (pinfunction "24_24") (pintype "bidirectional"))
      (node (ref "J23") (pin "3") (pinfunction "3_3") (pintype "bidirectional"))
    )
    (net (code "7") (name "/SENSC1_2") (class "Default")
      (node (ref "J15") (pin "9") (pinfunction "9_9") (pintype "bidirectional"))
      (node (ref "J23") (pin "2") (pinfunction "2_2") (pintype "bidirectional"))
    )
    (net (code "8") (name "/SENSC2_1") (class "Default")
      (node (ref "J15") (pin "25") (pinfunction "25_25") (pintype "bidirectional"))
      (node (ref "J26") (pin "7") (pinfunction "7_7") (pintype "bidirectional"))
    )
    (net (code "9") (name "/SENSC2_2") (class "Default")
      (node (ref "J15") (pin "10") (pinfunction "10_10") (pintype "bidirectional"))
      (node (ref "J26") (pin "6") (pinfunction "6_6") (pintype "bidirectional"))
    )
    (net (code "10") (name "/SENSC3_1") (class "Default")
      (node (ref "J15") (pin "26") (pinfunction "26_26") (pintype "bidirectional"))
      (node (ref "J26") (pin "3") (pinfunction "3_3") (pintype "bidirectional"))
    )
    (net (code "11") (name "/SENSC3_2") (class "Default")
      (node (ref "J15") (pin "11") (pinfunction "11_11") (pintype "bidirectional"))
      (node (ref "J26") (pin "2") (pinfunction "2_2") (pintype "bidirectional"))
    )
    (net (code "12") (name "/SENSC4_1") (class "Default")
      (node (ref "J15") (pin "27") (pinfunction "27_27") (pintype "bidirectional"))
      (node (ref "J24") (pin "7") (pinfunction "7_7") (pintype "bidirectional"))
    )
    (net (code "13") (name "/SENSC4_2") (class "Default")
      (node (ref "J15") (pin "12") (pinfunction "12_12") (pintype "bidirectional"))
      (node (ref "J24") (pin "6") (pinfunction "6_6") (pintype "bidirectional"))
    )
    (net (code "14") (name "/SENSC5_1") (class "Default")
      (node (ref "J15") (pin "28") (pinfunction "28_28") (pintype "bidirectional"))
      (node (ref "J24") (pin "3") (pinfunction "3_3") (pintype "bidirectional"))
    )
    (net (code "15") (name "/SENSC5_2") (class "Default")
      (node (ref "J15") (pin "13") (pinfunction "13_13") (pintype "bidirectional"))
      (node (ref "J24") (pin "2") (pinfunction "2_2") (pintype "bidirectional"))
    )
    (net (code "16") (name "/SENSC6_1") (class "Default")
      (node (ref "J15") (pin "29") (pinfunction "29_29") (pintype "bidirectional"))
      (node (ref "J27") (pin "7") (pinfunction "7_7") (pintype "bidirectional"))
    )
    (net (code "17") (name "/SENSC6_2") (class "Default")
      (node (ref "J15") (pin "14") (pinfunction "14_14") (pintype "bidirectional"))
      (node (ref "J27") (pin "6") (pinfunction "6_6") (pintype "bidirectional"))
    )
    (net (code "18") (name "/SENSC7_1") (class "Default")
      (node (ref "J15") (pin "30") (pinfunction "30_30") (pintype "bidirectional"))
      (node (ref "J27") (pin "3") (pinfunction "3_3") (pintype "bidirectional"))
    )
    (net (code "19") (name "/SENSC7_2") (class "Default")
      (node (ref "J15") (pin "15") (pinfunction "15_15") (pintype "bidirectional"))
      (node (ref "J27") (pin "2") (pinfunction "2_2") (pintype "bidirectional"))
    )
    (net (code "20") (name "/TECC0+") (class "Default")
      (node (ref "J14") (pin "5") (pinfunction "5_5") (pintype "bidirectional"))
      (node (ref "J15") (pin "31") (pinfunction "31_31") (pintype "bidirectional"))
      (node (ref "J15") (pin "32") (pinfunction "32_32") (pintype "bidirectional"))
    )
    (net (code "21") (name "/TECC0-") (class "Default")
      (node (ref "J14") (pin "4") (pinfunction "4_4") (pintype "bidirectional"))
      (node (ref "J15") (pin "1") (pinfunction "1_1") (pintype "bidirectional"))
      (node (ref "J15") (pin "16") (pinfunction "16_16") (pintype "bidirectional"))
    )
    (net (code "22") (name "/TECC1+") (class "Default")
      (node (ref "J14") (pin "2") (pinfunction "2_2") (pintype "bidirectional"))
      (node (ref "J15") (pin "17") (pinfunction "17_17") (pintype "bidirectional"))
      (node (ref "J15") (pin "2") (pinfunction "2_2") (pintype "bidirectional"))
    )
    (net (code "23") (name "/TECC1-") (class "Default")
      (node (ref "J14") (pin "1") (pinfunction "1_1") (pintype "bidirectional"))
      (node (ref "J15") (pin "18") (pinfunction "18_18") (pintype "bidirectional"))
      (node (ref "J15") (pin "3") (pinfunction "3_3") (pintype "bidirectional"))
    )
    (net (code "24") (name "/TECC2+") (class "Default")
      (node (ref "J15") (pin "19") (pinfunction "19_19") (pintype "bidirectional"))
      (node (ref "J15") (pin "4") (pinfunction "4_4") (pintype "bidirectional"))
      (node (ref "J16") (pin "5") (pinfunction "5_5") (pintype "bidirectional"))
    )
    (net (code "25") (name "/TECC2-") (class "Default")
      (node (ref "J15") (pin "20") (pinfunction "20_20") (pintype "bidirectional"))
      (node (ref "J15") (pin "5") (pinfunction "5_5") (pintype "bidirectional"))
      (node (ref "J16") (pin "4") (pinfunction "4_4") (pintype "bidirectional"))
    )
    (net (code "26") (name "/TECC3+") (class "Default")
      (node (ref "J15") (pin "21") (pinfunction "21_21") (pintype "bidirectional"))
      (node (ref "J15") (pin "6") (pinfunction "6_6") (pintype "bidirectional"))
      (node (ref "J16") (pin "2") (pinfunction "2_2") (pintype "bidirectional"))
    )
    (net (code "27") (name "/TECC3-") (class "Default")
      (node (ref "J15") (pin "22") (pinfunction "22_22") (pintype "bidirectional"))
      (node (ref "J15") (pin "7") (pinfunction "7_7") (pintype "bidirectional"))
      (node (ref "J16") (pin "1") (pinfunction "1_1") (pintype "bidirectional"))
    )
    (net (code "28") (name "/Vrefc0+") (class "Default")
      (node (ref "J15") (pin "37") (pinfunction "37_37") (pintype "bidirectional"))
    )
    (net (code "29") (name "/Vrefc0-") (class "Default")
      (node (ref "J15") (pin "38") (pinfunction "38_38") (pintype "bidirectional"))
    )
    (net (code "30") (name "/Vrefc1+") (class "Default")
      (node (ref "J15") (pin "39") (pinfunction "39_39") (pintype "bidirectional"))
    )
    (net (code "31") (name "/Vrefc1-") (class "Default")
      (node (ref "J15") (pin "40") (pinfunction "40_40") (pintype "bidirectional"))
    )
    (net (code "32") (name "/Vrefc2+") (class "Default")
      (node (ref "J15") (pin "41") (pinfunction "41_41") (pintype "bidirectional"))
    )
    (net (code "33") (name "/Vrefc2-") (class "Default")
      (node (ref "J15") (pin "42") (pinfunction "42_42") (pintype "bidirectional"))
    )
    (net (code "34") (name "/Vrefc3+") (class "Default")
      (node (ref "J15") (pin "43") (pinfunction "43_43") (pintype "bidirectional"))
    )
    (net (code "35") (name "/Vrefc3-") (class "Default")
      (node (ref "J15") (pin "44") (pinfunction "44_44") (pintype "bidirectional"))
    )
    (net (code "36") (name "GND") (class "Default")
      (node (ref "C116") (pin "1") (pinfunction "1_1") (pintype "passive"))
      (node (ref "C124") (pin "2") (pinfunction "2_2") (pintype "passive"))
      (node (ref "C125") (pin "1") (pinfunction "1_1") (pintype "passive"))
      (node (ref "C132") (pin "2") (pinfunction "2_2") (pintype "passive"))
      (node (ref "C133") (pin "1") (pinfunction "1_1") (pintype "passive"))
      (node (ref "C134") (pin "1") (pinfunction "1_1") (pintype "passive"))
      (node (ref "C135") (pin "1") (pinfunction "1_1") (pintype "passive"))
      (node (ref "C142") (pin "1") (pinfunction "1_1") (pintype "passive"))
      (node (ref "C143") (pin "1") (pinfunction "1_1") (pintype "passive"))
      (node (ref "D35") (pin "2") (pinfunction "GND_2") (pintype "power_in"))
      (node (ref "IC10") (pin "1") (pinfunction "GND_1") (pintype "power_in"))
      (node (ref "IC10") (pin "4") (pinfunction "GND_4") (pintype "power_in"))
      (node (ref "IC10") (pin "7") (pinfunction "GND_7") (pintype "power_in"))
      (node (ref "IC10") (pin "8") (pinfunction "GND_8") (pintype "power_in"))
      (node (ref "IC20") (pin "2") (pinfunction "VSS_2") (pintype "power_in"))
      (node (ref "IC21") (pin "2") (pinfunction "GND_2") (pintype "power_in"))
      (node (ref "IC24") (pin "4") (pinfunction "-V_4") (pintype "power_in"))
      (node (ref "IC25") (pin "4") (pinfunction "-V_4") (pintype "power_in"))
      (node (ref "IC26") (pin "4") (pinfunction "-V_4") (pintype "power_in"))
      (node (ref "IC27") (pin "4") (pinfunction "-V_4") (pintype "power_in"))
      (node (ref "J14") (pin "3") (pinfunction "3_3") (pintype "bidirectional"))
      (node (ref "J15") (pin "36") (pinfunction "36_36") (pintype "bidirectional"))
      (node (ref "J15") (pin "45") (pinfunction "45_45") (pintype "passive"))
      (node (ref "J15") (pin "46") (pinfunction "46_46") (pintype "passive"))
      (node (ref "J16") (pin "3") (pinfunction "3_3") (pintype "bidirectional"))
      (node (ref "R188") (pin "1") (pinfunction "1_1") (pintype "passive"))
      (node (ref "R189") (pin "1") (pinfunction "1_1") (pintype "passive"))
      (node (ref "R200") (pin "1") (pinfunction "1_1") (pintype "passive"))
      (node (ref "R201") (pin "1") (pinfunction "1_1") (pintype "passive"))
      (node (ref "R208") (pin "1") (pinfunction "1_1") (pintype "passive"))
      (node (ref "R209") (pin "1") (pinfunction "1_1") (pintype "passive"))
      (node (ref "R216") (pin "1") (pinfunction "1_1") (pintype "passive"))
      (node (ref "R217") (pin "1") (pinfunction "1_1") (pintype "passive"))
    )
    (net (code "37") (name "Net-(IC21-EN)") (class "Default")
      (node (ref "C124") (pin "1") (pinfunction "1_1") (pintype "passive"))
      (node (ref "IC21") (pin "1") (pinfunction "VIN_1") (pintype "input"))
      (node (ref "IC21") (pin "3") (pinfunction "EN_3") (pintype "input"))
      (node (ref "R45") (pin "2") (pinfunction "2_2") (pintype "passive"))
    )
    (net (code "38") (name "Net-(IC24A-+IN_A)") (class "Default")
      (node (ref "IC24") (pin "3") (pinfunction "+IN_A_3") (pintype "input"))
      (node (ref "R184") (pin "2") (pinfunction "2_2") (pintype "passive"))
    )
    (net (code "39") (name "Net-(IC24A--IN_A)") (class "Default")
      (node (ref "C136") (pin "1") (pinfunction "1_1") (pintype "passive"))
      (node (ref "IC24") (pin "2") (pinfunction "-IN_A_2") (pintype "input"))
      (node (ref "R186") (pin "2") (pinfunction "2_2") (pintype "passive"))
    )
    (net (code "40") (name "Net-(IC24A-OUT_A)") (class "Default")
      (node (ref "C136") (pin "2") (pinfunction "2_2") (pintype "passive"))
      (node (ref "IC24") (pin "1") (pinfunction "OUT_A_1") (pintype "output"))
      (node (ref "R182") (pin "1") (pinfunction "1_1") (pintype "passive"))
    )
    (net (code "41") (name "Net-(IC24B-+IN_B)") (class "Default")
      (node (ref "IC24") (pin "5") (pinfunction "+IN_B_5") (pintype "input"))
      (node (ref "R192") (pin "2") (pinfunction "2_2") (pintype "passive"))
    )
    (net (code "42") (name "Net-(IC24B--IN_B)") (class "Default")
      (node (ref "C140") (pin "1") (pinfunction "1_1") (pintype "passive"))
      (node (ref "IC24") (pin "6") (pinfunction "-IN_B_6") (pintype "input"))
      (node (ref "R198") (pin "2") (pinfunction "2_2") (pintype "passive"))
    )
    (net (code "43") (name "Net-(IC24B-OUT_B)") (class "Default")
      (node (ref "C140") (pin "2") (pinfunction "2_2") (pintype "passive"))
      (node (ref "IC24") (pin "7") (pinfunction "OUT_B_7") (pintype "output"))
      (node (ref "R190") (pin "1") (pinfunction "1_1") (pintype "passive"))
    )
    (net (code "44") (name "Net-(IC25A-+IN_A)") (class "Default")
      (node (ref "IC25") (pin "3") (pinfunction "+IN_A_3") (pintype "input"))
      (node (ref "R185") (pin "2") (pinfunction "2_2") (pintype "passive"))
    )
    (net (code "45") (name "Net-(IC25A--IN_A)") (class "Default")
      (node (ref "C137") (pin "1") (pinfunction "1_1") (pintype "passive"))
      (node (ref "IC25") (pin "2") (pinfunction "-IN_A_2") (pintype "input"))
      (node (ref "R187") (pin "2") (pinfunction "2_2") (pintype "passive"))
    )
    (net (code "46") (name "Net-(IC25A-OUT_A)") (class "Default")
      (node (ref "C137") (pin "2") (pinfunction "2_2") (pintype "passive"))
      (node (ref "IC25") (pin "1") (pinfunction "OUT_A_1") (pintype "output"))
      (node (ref "R183") (pin "1") (pinfunction "1_1") (pintype "passive"))
    )
    (net (code "47") (name "Net-(IC25B-+IN_B)") (class "Default")
      (node (ref "IC25") (pin "5") (pinfunction "+IN_B_5") (pintype "input"))
      (node (ref "R193") (pin "2") (pinfunction "2_2") (pintype "passive"))
    )
    (net (code "48") (name "Net-(IC25B--IN_B)") (class "Default")
      (node (ref "C141") (pin "1") (pinfunction "1_1") (pintype "passive"))
      (node (ref "IC25") (pin "6") (pinfunction "-IN_B_6") (pintype "input"))
      (node (ref "R199") (pin "2") (pinfunction "2_2") (pintype "passive"))
    )
    (net (code "49") (name "Net-(IC25B-OUT_B)") (class "Default")
      (node (ref "C141") (pin "2") (pinfunction "2_2") (pintype "passive"))
      (node (ref "IC25") (pin "7") (pinfunction "OUT_B_7") (pintype "output"))
      (node (ref "R191") (pin "1") (pinfunction "1_1") (pintype "passive"))
    )
    (net (code "50") (name "Net-(IC26A-+IN_A)") (class "Default")
      (node (ref "IC26") (pin "3") (pinfunction "+IN_A_3") (pintype "input"))
      (node (ref "R204") (pin "2") (pinfunction "2_2") (pintype "passive"))
    )
    (net (code "51") (name "Net-(IC26A--IN_A)") (class "Default")
      (node (ref "C149") (pin "1") (pinfunction "1_1") (pintype "passive"))
      (node (ref "IC26") (pin "2") (pinfunction "-IN_A_2") (pintype "input"))
      (node (ref "R206") (pin "2") (pinfunction "2_2") (pintype "passive"))
    )
    (net (code "52") (name "Net-(IC26A-OUT_A)") (class "Default")
      (node (ref "C149") (pin "2") (pinfunction "2_2") (pintype "passive"))
      (node (ref "IC26") (pin "1") (pinfunction "OUT_A_1") (pintype "output"))
      (node (ref "R202") (pin "1") (pinfunction "1_1") (pintype "passive"))
    )
    (net (code "53") (name "Net-(IC26B-+IN_B)") (class "Default")
      (node (ref "IC26") (pin "5") (pinfunction "+IN_B_5") (pintype "input"))
      (node (ref "R212") (pin "2") (pinfunction "2_2") (pintype "passive"))
    )
    (net (code "54") (name "Net-(IC26B--IN_B)") (class "Default")
      (node (ref "C153") (pin "1") (pinfunction "1_1") (pintype "passive"))
      (node (ref "IC26") (pin "6") (pinfunction "-IN_B_6") (pintype "input"))
      (node (ref "R214") (pin "2") (pinfunction "2_2") (pintype "passive"))
    )
    (net (code "55") (name "Net-(IC26B-OUT_B)") (class "Default")
      (node (ref "C153") (pin "2") (pinfunction "2_2") (pintype "passive"))
      (node (ref "IC26") (pin "7") (pinfunction "OUT_B_7") (pintype "output"))
      (node (ref "R210") (pin "1") (pinfunction "1_1") (pintype "passive"))
    )
    (net (code "56") (name "Net-(IC27A-+IN_A)") (class "Default")
      (node (ref "IC27") (pin "3") (pinfunction "+IN_A_3") (pintype "input"))
      (node (ref "R205") (pin "2") (pinfunction "2_2") (pintype "passive"))
    )
    (net (code "57") (name "Net-(IC27A--IN_A)") (class "Default")
      (node (ref "C150") (pin "1") (pinfunction "1_1") (pintype "passive"))
      (node (ref "IC27") (pin "2") (pinfunction "-IN_A_2") (pintype "input"))
      (node (ref "R207") (pin "2") (pinfunction "2_2") (pintype "passive"))
    )
    (net (code "58") (name "Net-(IC27A-OUT_A)") (class "Default")
      (node (ref "C150") (pin "2") (pinfunction "2_2") (pintype "passive"))
      (node (ref "IC27") (pin "1") (pinfunction "OUT_A_1") (pintype "output"))
      (node (ref "R203") (pin "1") (pinfunction "1_1") (pintype "passive"))
    )
    (net (code "59") (name "Net-(IC27B-+IN_B)") (class "Default")
      (node (ref "IC27") (pin "5") (pinfunction "+IN_B_5") (pintype "input"))
      (node (ref "R213") (pin "2") (pinfunction "2_2") (pintype "passive"))
    )
    (net (code "60") (name "Net-(IC27B--IN_B)") (class "Default")
      (node (ref "C154") (pin "1") (pinfunction "1_1") (pintype "passive"))
      (node (ref "IC27") (pin "6") (pinfunction "-IN_B_6") (pintype "input"))
      (node (ref "R215") (pin "2") (pinfunction "2_2") (pintype "passive"))
    )
    (net (code "61") (name "Net-(IC27B-OUT_B)") (class "Default")
      (node (ref "C154") (pin "2") (pinfunction "2_2") (pintype "passive"))
      (node (ref "IC27") (pin "7") (pinfunction "OUT_B_7") (pintype "output"))
      (node (ref "R211") (pin "1") (pinfunction "1_1") (pintype "passive"))
    )
    (net (code "62") (name "Net-(J23-Pad1)") (class "Default")
      (node (ref "J23") (pin "1") (pinfunction "1_1") (pintype "bidirectional"))
      (node (ref "R198") (pin "1") (pinfunction "1_1") (pintype "passive"))
      (node (ref "R200") (pin "2") (pinfunction "2_2") (pintype "passive"))
    )
    (net (code "63") (name "Net-(J23-Pad4)") (class "Default")
      (node (ref "J23") (pin "4") (pinfunction "4_4") (pintype "bidirectional"))
      (node (ref "R190") (pin "2") (pinfunction "2_2") (pintype "passive"))
    )
    (net (code "64") (name "Net-(J23-Pad5)") (class "Default")
      (node (ref "J23") (pin "5") (pinfunction "5_5") (pintype "bidirectional"))
      (node (ref "R186") (pin "1") (pinfunction "1_1") (pintype "passive"))
      (node (ref "R188") (pin "2") (pinfunction "2_2") (pintype "passive"))
    )
    (net (code "65") (name "Net-(J23-Pad8)") (class "Default")
      (node (ref "J23") (pin "8") (pinfunction "8_8") (pintype "bidirectional"))
      (node (ref "R182") (pin "2") (pinfunction "2_2") (pintype "passive"))
    )
    (net (code "66") (name "Net-(J24-Pad1)") (class "Default")
      (node (ref "J24") (pin "1") (pinfunction "1_1") (pintype "bidirectional"))
      (node (ref "R199") (pin "1") (pinfunction "1_1") (pintype "passive"))
      (node (ref "R201") (pin "2") (pinfunction "2_2") (pintype "passive"))
    )
    (net (code "67") (name "Net-(J24-Pad4)") (class "Default")
      (node (ref "J24") (pin "4") (pinfunction "4_4") (pintype "bidirectional"))
      (node (ref "R191") (pin "2") (pinfunction "2_2") (pintype "passive"))
    )
    (net (code "68") (name "Net-(J24-Pad5)") (class "Default")
      (node (ref "J24") (pin "5") (pinfunction "5_5") (pintype "bidirectional"))
      (node (ref "R187") (pin "1") (pinfunction "1_1") (pintype "passive"))
      (node (ref "R189") (pin "2") (pinfunction "2_2") (pintype "passive"))
    )
    (net (code "69") (name "Net-(J24-Pad8)") (class "Default")
      (node (ref "J24") (pin "8") (pinfunction "8_8") (pintype "bidirectional"))
      (node (ref "R183") (pin "2") (pinfunction "2_2") (pintype "passive"))
    )
    (net (code "70") (name "Net-(J26-Pad1)") (class "Default")
      (node (ref "J26") (pin "1") (pinfunction "1_1") (pintype "bidirectional"))
      (node (ref "R214") (pin "1") (pinfunction "1_1") (pintype "passive"))
      (node (ref "R216") (pin "2") (pinfunction "2_2") (pintype "passive"))
    )
    (net (code "71") (name "Net-(J26-Pad4)") (class "Default")
      (node (ref "J26") (pin "4") (pinfunction "4_4") (pintype "bidirectional"))
      (node (ref "R210") (pin "2") (pinfunction "2_2") (pintype "passive"))
    )
    (net (code "72") (name "Net-(J26-Pad5)") (class "Default")
      (node (ref "J26") (pin "5") (pinfunction "5_5") (pintype "bidirectional"))
      (node (ref "R206") (pin "1") (pinfunction "1_1") (pintype "passive"))
      (node (ref "R208") (pin "2") (pinfunction "2_2") (pintype "passive"))
    )
    (net (code "73") (name "Net-(J26-Pad8)") (class "Default")
      (node (ref "J26") (pin "8") (pinfunction "8_8") (pintype "bidirectional"))
      (node (ref "R202") (pin "2") (pinfunction "2_2") (pintype "passive"))
    )
    (net (code "74") (name "Net-(J27-Pad1)") (class "Default")
      (node (ref "J27") (pin "1") (pinfunction "1_1") (pintype "bidirectional"))
      (node (ref "R215") (pin "1") (pinfunction "1_1") (pintype "passive"))
      (node (ref "R217") (pin "2") (pinfunction "2_2") (pintype "passive"))
    )
    (net (code "75") (name "Net-(J27-Pad4)") (class "Default")
      (node (ref "J27") (pin "4") (pinfunction "4_4") (pintype "bidirectional"))
      (node (ref "R211") (pin "2") (pinfunction "2_2") (pintype "passive"))
    )
    (net (code "76") (name "Net-(J27-Pad5)") (class "Default")
      (node (ref "J27") (pin "5") (pinfunction "5_5") (pintype "bidirectional"))
      (node (ref "R207") (pin "1") (pinfunction "1_1") (pintype "passive"))
      (node (ref "R209") (pin "2") (pinfunction "2_2") (pintype "passive"))
    )
    (net (code "77") (name "Net-(J27-Pad8)") (class "Default")
      (node (ref "J27") (pin "8") (pinfunction "8_8") (pintype "bidirectional"))
      (node (ref "R203") (pin "2") (pinfunction "2_2") (pintype "passive"))
    )
    (net (code "78") (name "P3V3_AFEC") (class "Default")
      (node (ref "C116") (pin "2") (pinfunction "2_2") (pintype "passive"))
      (node (ref "C125") (pin "2") (pinfunction "2_2") (pintype "passive"))
      (node (ref "D35") (pin "5") (pinfunction "VBUS_5") (pintype "power_in"))
      (node (ref "IC20") (pin "4") (pinfunction "VCC_4") (pintype "power_in"))
      (node (ref "IC21") (pin "5") (pinfunction "VOUT_5") (pintype "power_in"))
      (node (ref "TP14") (pin "1") (pinfunction "1_1") (pintype "bidirectional"))
    )
    (net (code "79") (name "P5V0_AFEC") (class "Default")
      (node (ref "C132") (pin "1") (pinfunction "1_1") (pintype "passive"))
      (node (ref "C134") (pin "2") (pinfunction "2_2") (pintype "passive"))
      (node (ref "C135") (pin "2") (pinfunction "2_2") (pintype "passive"))
      (node (ref "C142") (pin "2") (pinfunction "2_2") (pintype "passive"))
      (node (ref "C143") (pin "2") (pinfunction "2_2") (pintype "passive"))
      (node (ref "IC10") (pin "2") (pinfunction "VIN_2") (pintype "input"))
      (node (ref "IC10") (pin "3") (pinfunction "EN_3") (pintype "input"))
      (node (ref "IC24") (pin "8") (pinfunction "+V_8") (pintype "power_in"))
      (node (ref "IC25") (pin "8") (pinfunction "+V_8") (pintype "power_in"))
      (node (ref "IC26") (pin "8") (pinfunction "+V_8") (pintype "power_in"))
      (node (ref "IC27") (pin "8") (pinfunction "+V_8") (pintype "power_in"))
      (node (ref "J15") (pin "33") (pinfunction "33_33") (pintype "bidirectional"))
      (node (ref "R45") (pin "1") (pinfunction "1_1") (pintype "passive"))
    )
    (net (code "80") (name "unconnected-(D35-I{slash}O1-Pad1)") (class "Default")
      (node (ref "D35") (pin "1") (pinfunction "I/O1_1") (pintype "bidirectional+no_connect"))
    )
    (net (code "81") (name "unconnected-(D35-I{slash}O2-Pad3)") (class "Default")
      (node (ref "D35") (pin "3") (pinfunction "I/O2_3") (pintype "bidirectional+no_connect"))
    )
    (net (code "82") (name "unconnected-(IC10-NC-Pad5)") (class "Default")
      (node (ref "IC10") (pin "5") (pinfunction "NC_5") (pintype "passive"))
    )
    (net (code "83") (name "unconnected-(IC20-NC-Pad5)") (class "Default")
      (node (ref "IC20") (pin "5") (pinfunction "NC_5") (pintype "passive+no_connect"))
    )
    (net (code "84") (name "unconnected-(IC21-NC-Pad4)") (class "Default")
      (node (ref "IC21") (pin "4") (pinfunction "NC_4") (pintype "passive+no_connect"))
    )
  )
)
